# MCU_Ver1.net
KiCad netlist of a schematic drawn in Altium Designer
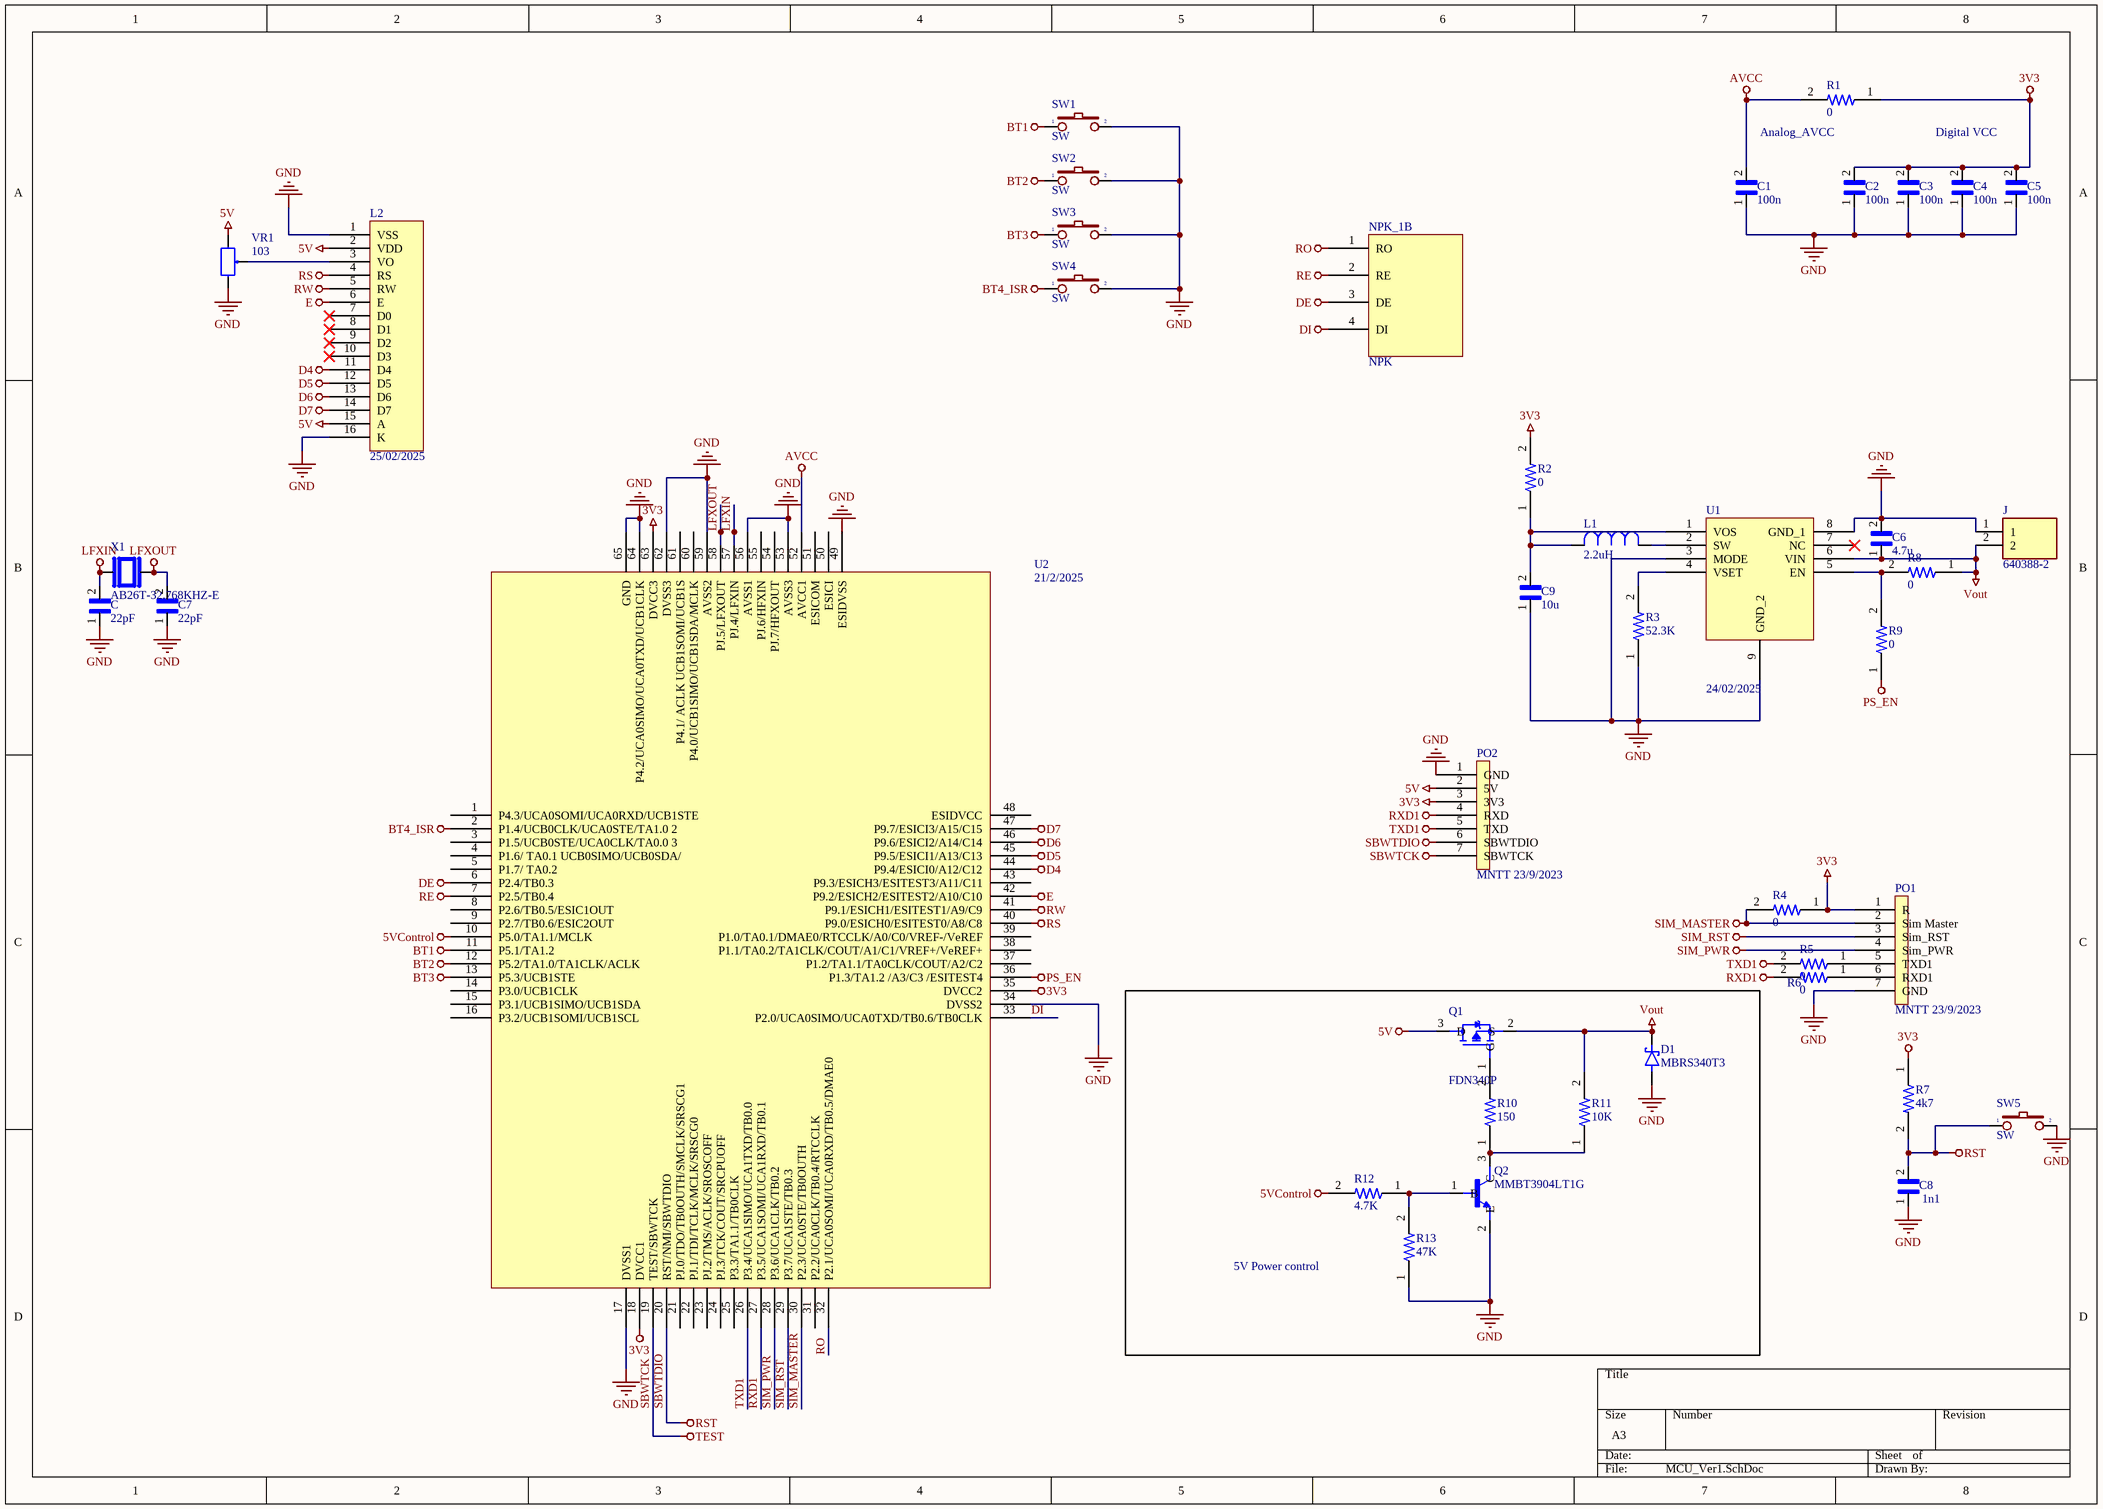
[diagram p0: MCU_Ver1.SchDoc]

(export (version "E")
  (design (tool "Eeschema 10.0.6"))
  (components
    (comp (ref "C")
      (value "22pF")
      (footprint "CAPC0603X33N")
      (description "SMD Capacitor X7R_EIA_ with Capacitance: 1000pF Tol. 10%. Rated Voltage: 50Vdc")
      (fields (field (name "DIGI-KEY_PART_NUMBER") "490-10682-1-ND") (field (name "MP") "GRM033R71H102KA12D"))
      (libsource (lib "GRM033R71H102KA12D") (part "GRM033R71H102KA12D"))
    )
    (comp (ref "C1")
      (value "100n")
      (footprint "CAPC0603X33N")
      (description "SMD Capacitor X7R_EIA_ with Capacitance: 1000pF Tol. 10%. Rated Voltage: 50Vdc")
      (fields (field (name "DIGI-KEY_PART_NUMBER") "490-10682-1-ND") (field (name "MP") "GRM033R71H102KA12D"))
      (libsource (lib "GRM033R71H102KA12D") (part "GRM033R71H102KA12D"))
    )
    (comp (ref "C2")
      (value "100n")
      (footprint "CAPC0603X33N")
      (description "SMD Capacitor X7R_EIA_ with Capacitance: 1000pF Tol. 10%. Rated Voltage: 50Vdc")
      (fields (field (name "DIGI-KEY_PART_NUMBER") "490-10682-1-ND") (field (name "MP") "GRM033R71H102KA12D"))
      (libsource (lib "GRM033R71H102KA12D") (part "GRM033R71H102KA12D"))
    )
    (comp (ref "C3")
      (value "100n")
      (footprint "CAPC0603X33N")
      (description "SMD Capacitor X7R_EIA_ with Capacitance: 1000pF Tol. 10%. Rated Voltage: 50Vdc")
      (fields (field (name "DIGI-KEY_PART_NUMBER") "490-10682-1-ND") (field (name "MP") "GRM033R71H102KA12D"))
      (libsource (lib "GRM033R71H102KA12D") (part "GRM033R71H102KA12D"))
    )
    (comp (ref "C4")
      (value "100n")
      (footprint "CAPC0603X33N")
      (description "SMD Capacitor X7R_EIA_ with Capacitance: 1000pF Tol. 10%. Rated Voltage: 50Vdc")
      (fields (field (name "DIGI-KEY_PART_NUMBER") "490-10682-1-ND") (field (name "MP") "GRM033R71H102KA12D"))
      (libsource (lib "GRM033R71H102KA12D") (part "GRM033R71H102KA12D"))
    )
    (comp (ref "C5")
      (value "100n")
      (footprint "CAPC0603X33N")
      (description "SMD Capacitor X7R_EIA_ with Capacitance: 1000pF Tol. 10%. Rated Voltage: 50Vdc")
      (fields (field (name "DIGI-KEY_PART_NUMBER") "490-10682-1-ND") (field (name "MP") "GRM033R71H102KA12D"))
      (libsource (lib "GRM033R71H102KA12D") (part "GRM033R71H102KA12D"))
    )
    (comp (ref "C6")
      (value "4.7u")
      (footprint "CAPC0603X33N")
      (description "SMD Capacitor X7R_EIA_ with Capacitance: 1000pF Tol. 10%. Rated Voltage: 50Vdc")
      (fields (field (name "DIGI-KEY_PART_NUMBER") "490-10682-1-ND") (field (name "MP") "GRM033R71H102KA12D"))
      (libsource (lib "GRM033R71H102KA12D") (part "GRM033R71H102KA12D"))
    )
    (comp (ref "C7")
      (value "22pF")
      (footprint "CAPC0603X33N")
      (description "SMD Capacitor X7R_EIA_ with Capacitance: 1000pF Tol. 10%. Rated Voltage: 50Vdc")
      (fields (field (name "DIGI-KEY_PART_NUMBER") "490-10682-1-ND") (field (name "MP") "GRM033R71H102KA12D"))
      (libsource (lib "GRM033R71H102KA12D") (part "GRM033R71H102KA12D"))
    )
    (comp (ref "C8")
      (value "1n1")
      (footprint "CAPC0603X33N")
      (description "SMD Capacitor X7R_EIA_ with Capacitance: 1000pF Tol. 10%. Rated Voltage: 50Vdc")
      (fields (field (name "DIGI-KEY_PART_NUMBER") "490-10682-1-ND") (field (name "MP") "GRM033R71H102KA12D"))
      (libsource (lib "GRM033R71H102KA12D") (part "GRM033R71H102KA12D"))
    )
    (comp (ref "C9")
      (value "10u")
      (footprint "CAPC0603X33N")
      (description "SMD Capacitor X7R_EIA_ with Capacitance: 1000pF Tol. 10%. Rated Voltage: 50Vdc")
      (fields (field (name "DIGI-KEY_PART_NUMBER") "490-10682-1-ND") (field (name "MP") "GRM033R71H102KA12D"))
      (libsource (lib "GRM033R71H102KA12D") (part "GRM033R71H102KA12D"))
    )
    (comp (ref "D1")
      (value "MBRS340T3")
      (footprint "DIOM7959X261N")
      (description "Diode Schottky 40V 4A Surface Mount SMC")
      (fields (field (name "MF") "ON Semiconductor"))
      (libsource (lib "MBRS340T3") (part "MBRS340T3"))
    )
    (comp (ref "J")
      (value "640388-2")
      (footprint "TE_640388-2")
      (description "Header; Conn; Interconnect System; PCB Plug; 2 Cont; Solder; MTA-156 Series; Straight")
      (fields (field (name "MF") "TE Connectivity"))
      (libsource (lib "640388-2") (part "640388-2"))
    )
    (comp (ref "L1")
      (value "2.2uH")
      (footprint "IND_CDRH127/LDNP-470MC_SUM")
      (description "47 ÂµH Shielded - Inductor 3.25 A 78mOhm Max Nonstandard")
      (fields (field (name "MF") "Sumida America") (field (name "MP") "CDRH127/LDNP-470MC"))
      (libsource (lib "CDRH127_LDNP-470MC") (part "CDRH127/LDNP-470MC"))
    )
    (comp (ref "L2")
      (value "25/02/2025")
      (footprint "PCBComponent_1")
      (libsource (lib "LCD1602") (part "LCD1602"))
    )
    (comp (ref "NPK_1")
      (value "NPK")
      (footprint "PCBComponent_1")
      (description "02/04/2024. NPK_?")
      (libsource (lib "NPK") (part "NPK"))
    )
    (comp (ref "PO1")
      (value "MNTT 23/9/2023")
      (footprint "PCBComponent_1")
      (libsource (lib "Port 7 pins") (part "Port 7 pins"))
    )
    (comp (ref "PO2")
      (value "MNTT 23/9/2023")
      (footprint "PCBComponent_1")
      (libsource (lib "Port 7 pins") (part "Port 7 pins"))
    )
    (comp (ref "Q1")
      (value "FDN340P")
      (footprint "SOT95P240X120-3N")
      (description "FDN340P Series 20V 70 mOhm Single P-Ch Logic Level PowerTrench Mosfet SSOT-3")
      (libsource (lib "FDN340P") (part "FDN340P"))
    )
    (comp (ref "Q2")
      (value "MMBT3904LT1G")
      (footprint "SOT95P240X111-3N")
      (description "Bipolar _BJT_ Transistor NPN 40V 200mA 300MHz 300mW Surface Mount SOT-23-3 _TO-236_")
      (fields (field (name "MF") "ON Semiconductor"))
      (libsource (lib "MMBT3904LT1G") (part "MMBT3904LT1G"))
    )
    (comp (ref "R1")
      (value "0")
      (footprint "RESC1608X50N")
      (description "RES SMD 180K OHM 5% 1/4W 0603")
      (fields (field (name "MP") "CRGS0603J180K"))
      (libsource (lib "CRGS0603J180K") (part "CRGS0603J180K"))
    )
    (comp (ref "R2")
      (value "0")
      (footprint "RESC1608X50N")
      (description "RES SMD 180K OHM 5% 1/4W 0603")
      (fields (field (name "MP") "CRGS0603J180K"))
      (libsource (lib "CRGS0603J180K") (part "CRGS0603J180K"))
    )
    (comp (ref "R3")
      (value "52.3K")
      (footprint "RESC1608X50N")
      (description "RES SMD 180K OHM 5% 1/4W 0603")
      (fields (field (name "MP") "CRGS0603J180K"))
      (libsource (lib "CRGS0603J180K") (part "CRGS0603J180K"))
    )
    (comp (ref "R4")
      (value "0")
      (footprint "RESC1608X50N")
      (description "RES SMD 180K OHM 5% 1/4W 0603")
      (fields (field (name "MP") "CRGS0603J180K"))
      (libsource (lib "CRGS0603J180K") (part "CRGS0603J180K"))
    )
    (comp (ref "R5")
      (value "0")
      (footprint "RESC1608X50N")
      (description "RES SMD 180K OHM 5% 1/4W 0603")
      (fields (field (name "MP") "CRGS0603J180K"))
      (libsource (lib "CRGS0603J180K") (part "CRGS0603J180K"))
    )
    (comp (ref "R6")
      (value "0")
      (footprint "RESC1608X50N")
      (description "RES SMD 180K OHM 5% 1/4W 0603")
      (fields (field (name "MP") "CRGS0603J180K"))
      (libsource (lib "CRGS0603J180K") (part "CRGS0603J180K"))
    )
    (comp (ref "R7")
      (value "4k7")
      (footprint "RESC1608X50N")
      (description "RES SMD 180K OHM 5% 1/4W 0603")
      (fields (field (name "MP") "CRGS0603J180K"))
      (libsource (lib "CRGS0603J180K") (part "CRGS0603J180K"))
    )
    (comp (ref "R8")
      (value "0")
      (footprint "RESC1608X50N")
      (description "RES SMD 180K OHM 5% 1/4W 0603")
      (fields (field (name "MP") "CRGS0603J180K"))
      (libsource (lib "CRGS0603J180K") (part "CRGS0603J180K"))
    )
    (comp (ref "R9")
      (value "0")
      (footprint "RESC1608X50N")
      (description "RES SMD 180K OHM 5% 1/4W 0603")
      (fields (field (name "MP") "CRGS0603J180K"))
      (libsource (lib "CRGS0603J180K") (part "CRGS0603J180K"))
    )
    (comp (ref "R10")
      (value "150")
      (footprint "CAPC0603X33N")
      (description "RES SMD 180K OHM 5% 1/4W 0603")
      (fields (field (name "MP") "CRGS0603J180K"))
      (libsource (lib "CRGS0603J180K") (part "CRGS0603J180K"))
    )
    (comp (ref "R11")
      (value "10K")
      (footprint "CAPC0603X33N")
      (description "RES SMD 180K OHM 5% 1/4W 0603")
      (fields (field (name "MP") "CRGS0603J180K"))
      (libsource (lib "CRGS0603J180K") (part "CRGS0603J180K"))
    )
    (comp (ref "R12")
      (value "4.7K")
      (footprint "CAPC0603X33N")
      (description "RES SMD 180K OHM 5% 1/4W 0603")
      (fields (field (name "MP") "CRGS0603J180K"))
      (libsource (lib "CRGS0603J180K") (part "CRGS0603J180K"))
    )
    (comp (ref "R13")
      (value "47K")
      (footprint "CAPC0603X33N")
      (description "RES SMD 180K OHM 5% 1/4W 0603")
      (fields (field (name "MP") "CRGS0603J180K"))
      (libsource (lib "CRGS0603J180K") (part "CRGS0603J180K"))
    )
    (comp (ref "SW1")
      (value "SW")
      (footprint "SW2")
      (description "Switch button 2 pin")
      (libsource (lib "syhaunguyen") (part "SW2"))
    )
    (comp (ref "SW2")
      (value "SW")
      (footprint "SW2")
      (description "Switch button 2 pin")
      (libsource (lib "syhaunguyen") (part "SW2"))
    )
    (comp (ref "SW3")
      (value "SW")
      (footprint "SW2")
      (description "Switch button 2 pin")
      (libsource (lib "syhaunguyen") (part "SW2"))
    )
    (comp (ref "SW4")
      (value "SW")
      (footprint "SW2")
      (description "Switch button 2 pin")
      (libsource (lib "syhaunguyen") (part "SW2"))
    )
    (comp (ref "SW5")
      (value "SW")
      (footprint "SW2")
      (description "Switch button 2 pin")
      (libsource (lib "syhaunguyen") (part "SW2"))
    )
    (comp (ref "U1")
      (value "24/02/2025")
      (footprint "SOP65P490X110-9N")
      (libsource (lib "TPS6282") (part "TPS62842DGRR"))
    )
    (comp (ref "U2")
      (value "21/2/2025")
      (footprint "IC_BQ500215RGCR")
      (libsource (lib "MSP430fr5989ver2") (part "MSP430FR5989_VER2"))
    )
    (comp (ref "VR1")
      (value "103")
      (footprint "VR")
      (description "Var Resistor")
      (libsource (lib "syhaunguyen") (part "VR"))
    )
    (comp (ref "X1")
      (value "AB26T-32.768KHZ-E")
      (footprint "XTAL_AB26T-32.768KHZ-E")
      (description "32.768kHz WATCH CRYSTAL, 6.2 x 02.1MM CYLINDER PACKAGE")
      (fields (field (name "MF") "Abracon LLC"))
      (libsource (lib "AB26T-32.768KHZ-E") (part "AB26T-32.768KHZ-E"))
    )
  )
  (nets
    (net (code "1") (name "3V3") (class "Default")
      (node (ref "C2") (pin "2") (pinfunction "2_2") (pintype "passive"))
      (node (ref "C3") (pin "2") (pinfunction "2_2") (pintype "passive"))
      (node (ref "C4") (pin "2") (pinfunction "2_2") (pintype "passive"))
      (node (ref "C5") (pin "2") (pinfunction "2_2") (pintype "passive"))
      (node (ref "PO1") (pin "1") (pinfunction "R_1") (pintype "passive"))
      (node (ref "PO2") (pin "3") (pinfunction "Sim_RST_3") (pintype "passive"))
      (node (ref "R1") (pin "1") (pinfunction "1_1") (pintype "passive"))
      (node (ref "R2") (pin "2") (pinfunction "2_2") (pintype "passive"))
      (node (ref "R4") (pin "1") (pinfunction "1_1") (pintype "passive"))
      (node (ref "R7") (pin "1") (pinfunction "1_1") (pintype "passive"))
      (node (ref "U2") (pin "18") (pinfunction "DVCC1_18") (pintype "passive"))
      (node (ref "U2") (pin "35") (pinfunction "DVCC2_35") (pintype "passive"))
      (node (ref "U2") (pin "63") (pinfunction "DVCC3_63") (pintype "passive"))
    )
    (net (code "2") (name "5V") (class "Default")
      (node (ref "L2") (pin "15") (pinfunction "A_15") (pintype "passive"))
      (node (ref "L2") (pin "2") (pinfunction "VDD_2") (pintype "passive"))
      (node (ref "PO2") (pin "2") (pinfunction "Sim_Master_2") (pintype "passive"))
      (node (ref "Q1") (pin "3") (pinfunction "D_3") (pintype "passive"))
      (node (ref "VR1") (pin "1") (pinfunction "1_1") (pintype "passive"))
    )
    (net (code "3") (name "5VControl") (class "Default")
      (node (ref "R12") (pin "2") (pinfunction "2_2") (pintype "passive"))
      (node (ref "U2") (pin "10") (pinfunction "P5.0/TA1.1/MCLK_10") (pintype "passive"))
    )
    (net (code "4") (name "AVCC") (class "Default")
      (node (ref "C1") (pin "2") (pinfunction "2_2") (pintype "passive"))
      (node (ref "R1") (pin "2") (pinfunction "2_2") (pintype "passive"))
      (node (ref "U2") (pin "52") (pinfunction "AVCC1_52") (pintype "passive"))
    )
    (net (code "5") (name "BT1") (class "Default")
      (node (ref "SW1") (pin "1") (pinfunction "1_1") (pintype "passive"))
      (node (ref "U2") (pin "11") (pinfunction "P5.1/TA1.2_11") (pintype "passive"))
    )
    (net (code "6") (name "BT2") (class "Default")
      (node (ref "SW2") (pin "1") (pinfunction "1_1") (pintype "passive"))
      (node (ref "U2") (pin "12") (pinfunction "P5.2/TA1.0/TA1CLK/ACLK_12") (pintype "passive"))
    )
    (net (code "7") (name "BT3") (class "Default")
      (node (ref "SW3") (pin "1") (pinfunction "1_1") (pintype "passive"))
      (node (ref "U2") (pin "13") (pinfunction "P5.3/UCB1STE_13") (pintype "passive"))
    )
    (net (code "8") (name "BT4_ISR") (class "Default")
      (node (ref "SW4") (pin "1") (pinfunction "1_1") (pintype "passive"))
      (node (ref "U2") (pin "2") (pinfunction "P1.4/UCB0CLK/UCA0STE/TA1.0_2_2") (pintype "passive"))
    )
    (net (code "9") (name "D4") (class "Default")
      (node (ref "L2") (pin "11") (pinfunction "D4_11") (pintype "passive"))
      (node (ref "U2") (pin "44") (pinfunction "_P9.4/ESICI0/A12/C12_44") (pintype "passive"))
    )
    (net (code "10") (name "D5") (class "Default")
      (node (ref "L2") (pin "12") (pinfunction "D5_12") (pintype "passive"))
      (node (ref "U2") (pin "45") (pinfunction "P9.5/ESICI1/A13/C13_45") (pintype "passive"))
    )
    (net (code "11") (name "D6") (class "Default")
      (node (ref "L2") (pin "13") (pinfunction "D6_13") (pintype "passive"))
      (node (ref "U2") (pin "46") (pinfunction "_P9.6/ESICI2/A14/C14_46") (pintype "passive"))
    )
    (net (code "12") (name "D7") (class "Default")
      (node (ref "L2") (pin "14") (pinfunction "D7_14") (pintype "passive"))
      (node (ref "U2") (pin "47") (pinfunction "P9.7/ESICI3/A15/C15_47") (pintype "passive"))
    )
    (net (code "13") (name "DE") (class "Default")
      (node (ref "NPK_1") (pin "3") (pinfunction "DE_3") (pintype "passive"))
      (node (ref "U2") (pin "6") (pinfunction "P2.4/TB0.3_6") (pintype "passive"))
    )
    (net (code "14") (name "DI") (class "Default")
      (node (ref "NPK_1") (pin "4") (pinfunction "DI_4") (pintype "passive"))
      (node (ref "U2") (pin "33") (pinfunction "P2.0/UCA0SIMO/UCA0TXD/TB0.6/TB0CLK_33") (pintype "passive"))
    )
    (net (code "15") (name "E") (class "Default")
      (node (ref "L2") (pin "6") (pinfunction "E_6") (pintype "passive"))
      (node (ref "U2") (pin "42") (pinfunction "_P9.2/ESICH2/ESITEST2/A10/C10_42") (pintype "passive"))
    )
    (net (code "16") (name "GND") (class "Default")
      (node (ref "C") (pin "1") (pinfunction "1_1") (pintype "passive"))
      (node (ref "C1") (pin "1") (pinfunction "1_1") (pintype "passive"))
      (node (ref "C2") (pin "1") (pinfunction "1_1") (pintype "passive"))
      (node (ref "C3") (pin "1") (pinfunction "1_1") (pintype "passive"))
      (node (ref "C4") (pin "1") (pinfunction "1_1") (pintype "passive"))
      (node (ref "C5") (pin "1") (pinfunction "1_1") (pintype "passive"))
      (node (ref "C6") (pin "2") (pinfunction "2_2") (pintype "passive"))
      (node (ref "C7") (pin "1") (pinfunction "1_1") (pintype "passive"))
      (node (ref "C8") (pin "1") (pinfunction "1_1") (pintype "passive"))
      (node (ref "C9") (pin "1") (pinfunction "1_1") (pintype "passive"))
      (node (ref "D1") (pin "A") (pinfunction "A_A") (pintype "passive"))
      (node (ref "J") (pin "1") (pinfunction "1_1") (pintype "passive"))
      (node (ref "L2") (pin "1") (pinfunction "VSS_1") (pintype "passive"))
      (node (ref "L2") (pin "16") (pinfunction "K_16") (pintype "passive"))
      (node (ref "PO1") (pin "7") (pinfunction "GND_7") (pintype "passive"))
      (node (ref "PO2") (pin "1") (pinfunction "R_1") (pintype "passive"))
      (node (ref "Q2") (pin "2") (pinfunction "E_2") (pintype "passive"))
      (node (ref "R13") (pin "1") (pinfunction "1_1") (pintype "passive"))
      (node (ref "R3") (pin "1") (pinfunction "1_1") (pintype "passive"))
      (node (ref "SW1") (pin "2") (pinfunction "2_2") (pintype "passive"))
      (node (ref "SW2") (pin "2") (pinfunction "2_2") (pintype "passive"))
      (node (ref "SW3") (pin "2") (pinfunction "2_2") (pintype "passive"))
      (node (ref "SW4") (pin "2") (pinfunction "2_2") (pintype "passive"))
      (node (ref "SW5") (pin "2") (pinfunction "2_2") (pintype "passive"))
      (node (ref "U1") (pin "3") (pinfunction "MODE_3") (pintype "passive"))
      (node (ref "U1") (pin "8") (pinfunction "GND_1_8") (pintype "passive"))
      (node (ref "U1") (pin "9") (pinfunction "GND_2_9") (pintype "passive"))
      (node (ref "U2") (pin "17") (pinfunction "DVSS1_17") (pintype "passive"))
      (node (ref "U2") (pin "34") (pinfunction "DVSS2_34") (pintype "passive"))
      (node (ref "U2") (pin "49") (pinfunction "ESIDVSS_49") (pintype "passive"))
      (node (ref "U2") (pin "53") (pinfunction "AVSS3_53") (pintype "passive"))
      (node (ref "U2") (pin "56") (pinfunction "AVSS1_56") (pintype "passive"))
      (node (ref "U2") (pin "59") (pinfunction "AVSS2_59") (pintype "passive"))
      (node (ref "U2") (pin "62") (pinfunction "DVSS3_62") (pintype "passive"))
      (node (ref "U2") (pin "64") (pinfunction "P4.2/UCA0SIMO/UCA0TXD/UCB1CLK_64") (pintype "passive"))
      (node (ref "U2") (pin "65") (pinfunction "GND_65") (pintype "passive"))
      (node (ref "VR1") (pin "3") (pinfunction "3_3") (pintype "passive"))
    )
    (net (code "17") (name "LFXIN") (class "Default")
      (node (ref "C") (pin "2") (pinfunction "2_2") (pintype "passive"))
      (node (ref "U2") (pin "57") (pinfunction "PJ.4/LFXIN_57") (pintype "passive"))
      (node (ref "X1") (pin "1") (pinfunction "1_1") (pintype "passive"))
    )
    (net (code "18") (name "LFXOUT") (class "Default")
      (node (ref "C7") (pin "2") (pinfunction "2_2") (pintype "passive"))
      (node (ref "U2") (pin "58") (pinfunction "PJ.5/LFXOUT_58") (pintype "passive"))
      (node (ref "X1") (pin "2") (pinfunction "2_2") (pintype "passive"))
    )
    (net (code "19") (name "Net-(L2-VO)") (class "Default")
      (node (ref "L2") (pin "3") (pinfunction "VO_3") (pintype "passive"))
      (node (ref "VR1") (pin "2") (pinfunction "2_2") (pintype "passive"))
    )
    (net (code "20") (name "Net-(PO1-RXD1)") (class "Default")
      (node (ref "PO1") (pin "6") (pinfunction "RXD1_6") (pintype "passive"))
      (node (ref "R6") (pin "1") (pinfunction "1_1") (pintype "passive"))
    )
    (net (code "21") (name "Net-(PO1-TXD1)") (class "Default")
      (node (ref "PO1") (pin "5") (pinfunction "TXD1_5") (pintype "passive"))
      (node (ref "R5") (pin "1") (pinfunction "1_1") (pintype "passive"))
    )
    (net (code "22") (name "Net-(Q1-G)") (class "Default")
      (node (ref "Q1") (pin "1") (pinfunction "G_1") (pintype "passive"))
      (node (ref "R10") (pin "2") (pinfunction "2_2") (pintype "passive"))
    )
    (net (code "23") (name "Net-(Q2-B)") (class "Default")
      (node (ref "Q2") (pin "1") (pinfunction "B_1") (pintype "passive"))
      (node (ref "R12") (pin "1") (pinfunction "1_1") (pintype "passive"))
      (node (ref "R13") (pin "2") (pinfunction "2_2") (pintype "passive"))
    )
    (net (code "24") (name "Net-(Q2-C)") (class "Default")
      (node (ref "Q2") (pin "3") (pinfunction "C_3") (pintype "passive"))
      (node (ref "R10") (pin "1") (pinfunction "1_1") (pintype "passive"))
      (node (ref "R11") (pin "1") (pinfunction "1_1") (pintype "passive"))
    )
    (net (code "25") (name "Net-(U1-EN)") (class "Default")
      (node (ref "R8") (pin "2") (pinfunction "2_2") (pintype "passive"))
      (node (ref "R9") (pin "2") (pinfunction "2_2") (pintype "passive"))
      (node (ref "U1") (pin "5") (pinfunction "EN_5") (pintype "passive"))
    )
    (net (code "26") (name "Net-(U1-SW)") (class "Default")
      (node (ref "L1") (pin "1") (pinfunction "1_1") (pintype "passive"))
      (node (ref "U1") (pin "2") (pinfunction "SW_2") (pintype "passive"))
    )
    (net (code "27") (name "Net-(U1-VOS)") (class "Default")
      (node (ref "C9") (pin "2") (pinfunction "2_2") (pintype "passive"))
      (node (ref "L1") (pin "2") (pinfunction "2_2") (pintype "passive"))
      (node (ref "R2") (pin "1") (pinfunction "1_1") (pintype "passive"))
      (node (ref "U1") (pin "1") (pinfunction "VOS_1") (pintype "passive"))
    )
    (net (code "28") (name "Net-(U1-VSET)") (class "Default")
      (node (ref "R3") (pin "2") (pinfunction "2_2") (pintype "passive"))
      (node (ref "U1") (pin "4") (pinfunction "VSET_4") (pintype "passive"))
    )
    (net (code "29") (name "PS_EN") (class "Default")
      (node (ref "R9") (pin "1") (pinfunction "1_1") (pintype "passive"))
      (node (ref "U2") (pin "36") (pinfunction "P1.3/TA1.2_/A3/C3_/ESITEST4_36") (pintype "passive"))
    )
    (net (code "30") (name "RE") (class "Default")
      (node (ref "NPK_1") (pin "2") (pinfunction "RE_2") (pintype "passive"))
      (node (ref "U2") (pin "7") (pinfunction "P2.5/TB0.4_7") (pintype "passive"))
    )
    (net (code "31") (name "RO") (class "Default")
      (node (ref "NPK_1") (pin "1") (pinfunction "RO_1") (pintype "passive"))
      (node (ref "U2") (pin "32") (pinfunction "P2.1/UCA0SOMI/UCA0RXD/TB0.5/DMAE0_32") (pintype "passive"))
    )
    (net (code "32") (name "RS") (class "Default")
      (node (ref "L2") (pin "4") (pinfunction "RS_4") (pintype "passive"))
      (node (ref "U2") (pin "40") (pinfunction "P9.0/ESICH0/ESITEST0/A8/C8_40") (pintype "passive"))
    )
    (net (code "33") (name "RST") (class "Default")
      (node (ref "C8") (pin "2") (pinfunction "2_2") (pintype "passive"))
      (node (ref "PO2") (pin "6") (pinfunction "RXD1_6") (pintype "passive"))
      (node (ref "R7") (pin "2") (pinfunction "2_2") (pintype "passive"))
      (node (ref "SW5") (pin "1") (pinfunction "1_1") (pintype "passive"))
      (node (ref "U2") (pin "20") (pinfunction "RST/NMI/SBWTDIO_20") (pintype "passive"))
    )
    (net (code "34") (name "RW") (class "Default")
      (node (ref "L2") (pin "5") (pinfunction "RW_5") (pintype "passive"))
      (node (ref "U2") (pin "41") (pinfunction "P9.1/ESICH1/ESITEST1/A9/C9_41") (pintype "passive"))
    )
    (net (code "35") (name "RXD1") (class "Default")
      (node (ref "PO2") (pin "4") (pinfunction "Sim_PWR_4") (pintype "passive"))
      (node (ref "R6") (pin "2") (pinfunction "2_2") (pintype "passive"))
      (node (ref "U2") (pin "27") (pinfunction "P3.5/UCA1SOMI/UCA1RXD/TB0.1_27") (pintype "passive"))
    )
    (net (code "36") (name "SBWTCK") (class "Default")
      (node (ref "PO2") (pin "7") (pinfunction "GND_7") (pintype "passive"))
      (node (ref "U2") (pin "19") (pinfunction "TEST/SBWTCK_19") (pintype "passive"))
    )
    (net (code "37") (name "SIM_MASTER") (class "Default")
      (node (ref "PO1") (pin "2") (pinfunction "Sim_Master_2") (pintype "passive"))
      (node (ref "R4") (pin "2") (pinfunction "2_2") (pintype "passive"))
      (node (ref "U2") (pin "30") (pinfunction "P2.3/UCA0STE/TB0OUTH_30") (pintype "passive"))
    )
    (net (code "38") (name "SIM_PWR") (class "Default")
      (node (ref "PO1") (pin "4") (pinfunction "Sim_PWR_4") (pintype "passive"))
      (node (ref "U2") (pin "28") (pinfunction "P3.6/UCA1CLK/TB0.2_28") (pintype "passive"))
    )
    (net (code "39") (name "SIM_RST") (class "Default")
      (node (ref "PO1") (pin "3") (pinfunction "Sim_RST_3") (pintype "passive"))
      (node (ref "U2") (pin "29") (pinfunction "P3.7/UCA1STE/TB0.3_29") (pintype "passive"))
    )
    (net (code "40") (name "TXD1") (class "Default")
      (node (ref "PO2") (pin "5") (pinfunction "TXD1_5") (pintype "passive"))
      (node (ref "R5") (pin "2") (pinfunction "2_2") (pintype "passive"))
      (node (ref "U2") (pin "26") (pinfunction "P3.4/UCA1SIMO/UCA1TXD/TB0.0_26") (pintype "passive"))
    )
    (net (code "41") (name "Vout") (class "Default")
      (node (ref "C6") (pin "1") (pinfunction "1_1") (pintype "passive"))
      (node (ref "D1") (pin "C") (pinfunction "K_C") (pintype "passive"))
      (node (ref "J") (pin "2") (pinfunction "2_2") (pintype "passive"))
      (node (ref "Q1") (pin "2") (pinfunction "S_2") (pintype "passive"))
      (node (ref "R11") (pin "2") (pinfunction "2_2") (pintype "passive"))
      (node (ref "R8") (pin "1") (pinfunction "1_1") (pintype "passive"))
      (node (ref "U1") (pin "6") (pinfunction "VIN_6") (pintype "passive"))
    )
    (net (code "42") (name "unconnected-(L2-D0-Pad7)") (class "Default")
      (node (ref "L2") (pin "7") (pinfunction "D0_7") (pintype "passive+no_connect"))
    )
    (net (code "43") (name "unconnected-(L2-D1-Pad8)") (class "Default")
      (node (ref "L2") (pin "8") (pinfunction "D1_8") (pintype "passive+no_connect"))
    )
    (net (code "44") (name "unconnected-(L2-D2-Pad9)") (class "Default")
      (node (ref "L2") (pin "9") (pinfunction "D2_9") (pintype "passive+no_connect"))
    )
    (net (code "45") (name "unconnected-(L2-D3-Pad10)") (class "Default")
      (node (ref "L2") (pin "10") (pinfunction "D3_10") (pintype "passive+no_connect"))
    )
    (net (code "46") (name "unconnected-(U1-NC-Pad7)") (class "Default")
      (node (ref "U1") (pin "7") (pinfunction "NC_7") (pintype "passive+no_connect"))
    )
    (net (code "47") (name "unconnected-(U2-ESICI-Pad50)") (class "Default")
      (node (ref "U2") (pin "50") (pinfunction "ESICI_50") (pintype "passive"))
    )
    (net (code "48") (name "unconnected-(U2-ESICOM-Pad51)") (class "Default")
      (node (ref "U2") (pin "51") (pinfunction "ESICOM_51") (pintype "passive"))
    )
    (net (code "49") (name "unconnected-(U2-ESIDVCC-Pad48)") (class "Default")
      (node (ref "U2") (pin "48") (pinfunction "ESIDVCC_48") (pintype "passive"))
    )
    (net (code "50") (name "unconnected-(U2-P1.0{slash}TA0.1{slash}DMAE0{slash}RTCCLK{slash}A0{slash}C0{slash}VREF-{slash}VeREF-Pad39)") (class "Default")
      (node (ref "U2") (pin "39") (pinfunction "P1.0/TA0.1/DMAE0/RTCCLK/A0/C0/VREF-/VeREF_39") (pintype "passive"))
    )
    (net (code "51") (name "unconnected-(U2-P1.2{slash}TA1.1{slash}TA0CLK{slash}COUT{slash}A2{slash}C2-Pad37)") (class "Default")
      (node (ref "U2") (pin "37") (pinfunction "P1.2/TA1.1/TA0CLK/COUT/A2/C2_37") (pintype "passive"))
    )
    (net (code "52") (name "unconnected-(U2-P1.5{slash}UCB0STE{slash}UCA0CLK{slash}TA0.0_3-Pad3)") (class "Default")
      (node (ref "U2") (pin "3") (pinfunction "P1.5/UCB0STE/UCA0CLK/TA0.0_3_3") (pintype "passive"))
    )
    (net (code "53") (name "unconnected-(U2-P1.6{slash}_TA0.1_UCB0SIMO{slash}UCB0SDA{slash}-Pad4)") (class "Default")
      (node (ref "U2") (pin "4") (pinfunction "P1.6/_TA0.1_UCB0SIMO/UCB0SDA/_4") (pintype "passive"))
    )
    (net (code "54") (name "unconnected-(U2-P1.7{slash}_TA0.2-Pad5)") (class "Default")
      (node (ref "U2") (pin "5") (pinfunction "P1.7/_TA0.2_5") (pintype "passive"))
    )
    (net (code "55") (name "unconnected-(U2-P2.2{slash}UCA0CLK{slash}TB0.4{slash}RTCCLK-Pad31)") (class "Default")
      (node (ref "U2") (pin "31") (pinfunction "P2.2/UCA0CLK/TB0.4/RTCCLK_31") (pintype "passive"))
    )
    (net (code "56") (name "unconnected-(U2-P2.6{slash}TB0.5{slash}ESIC1OUT-Pad8)") (class "Default")
      (node (ref "U2") (pin "8") (pinfunction "P2.6/TB0.5/ESIC1OUT_8") (pintype "passive"))
    )
    (net (code "57") (name "unconnected-(U2-P2.7{slash}TB0.6{slash}ESIC2OUT-Pad9)") (class "Default")
      (node (ref "U2") (pin "9") (pinfunction "P2.7/TB0.6/ESIC2OUT_9") (pintype "passive"))
    )
    (net (code "58") (name "unconnected-(U2-P3.0{slash}UCB1CLK-Pad14)") (class "Default")
      (node (ref "U2") (pin "14") (pinfunction "P3.0/UCB1CLK_14") (pintype "passive"))
    )
    (net (code "59") (name "unconnected-(U2-P3.1{slash}UCB1SIMO{slash}UCB1SDA-Pad15)") (class "Default")
      (node (ref "U2") (pin "15") (pinfunction "P3.1/UCB1SIMO/UCB1SDA_15") (pintype "passive"))
    )
    (net (code "60") (name "unconnected-(U2-P3.2{slash}UCB1SOMI{slash}UCB1SCL-Pad16)") (class "Default")
      (node (ref "U2") (pin "16") (pinfunction "P3.2/UCB1SOMI/UCB1SCL_16") (pintype "passive"))
    )
    (net (code "61") (name "unconnected-(U2-P3.3{slash}TA1.1{slash}TB0CLK-Pad25)") (class "Default")
      (node (ref "U2") (pin "25") (pinfunction "P3.3/TA1.1/TB0CLK_25") (pintype "passive"))
    )
    (net (code "62") (name "unconnected-(U2-P4.0{slash}UCB1SIMO{slash}UCB1SDA{slash}MCLK-Pad60)") (class "Default")
      (node (ref "U2") (pin "60") (pinfunction "P4.0/UCB1SIMO/UCB1SDA/MCLK_60") (pintype "passive"))
    )
    (net (code "63") (name "unconnected-(U2-P4.1{slash}_ACLK_UCB1SOMI{slash}UCB1S-Pad61)") (class "Default")
      (node (ref "U2") (pin "61") (pinfunction "P4.1/_ACLK_UCB1SOMI/UCB1S_61") (pintype "passive"))
    )
    (net (code "64") (name "unconnected-(U2-P4.3{slash}UCA0SOMI{slash}UCA0RXD{slash}UCB1STE-Pad1)") (class "Default")
      (node (ref "U2") (pin "1") (pinfunction "P4.3/UCA0SOMI/UCA0RXD/UCB1STE_1") (pintype "passive"))
    )
    (net (code "65") (name "unconnected-(U2-PJ.0{slash}TDO{slash}TB0OUTH{slash}SMCLK{slash}SRSCG1-Pad21)") (class "Default")
      (node (ref "U2") (pin "21") (pinfunction "PJ.0/TDO/TB0OUTH/SMCLK/SRSCG1_21") (pintype "passive"))
    )
    (net (code "66") (name "unconnected-(U2-PJ.1{slash}TDI{slash}TCLK{slash}MCLK{slash}SRSCG0-Pad22)") (class "Default")
      (node (ref "U2") (pin "22") (pinfunction "PJ.1/TDI/TCLK/MCLK/SRSCG0_22") (pintype "passive"))
    )
    (net (code "67") (name "unconnected-(U2-PJ.2{slash}TMS{slash}ACLK{slash}SROSCOFF-Pad23)") (class "Default")
      (node (ref "U2") (pin "23") (pinfunction "PJ.2/TMS/ACLK/SROSCOFF_23") (pintype "passive"))
    )
    (net (code "68") (name "unconnected-(U2-PJ.3{slash}TCK{slash}COUT{slash}SRCPUOFF-Pad24)") (class "Default")
      (node (ref "U2") (pin "24") (pinfunction "PJ.3/TCK/COUT/SRCPUOFF_24") (pintype "passive"))
    )
    (net (code "69") (name "unconnected-(U2-PJ.6{slash}HFXIN-Pad55)") (class "Default")
      (node (ref "U2") (pin "55") (pinfunction "PJ.6/HFXIN_55") (pintype "passive"))
    )
    (net (code "70") (name "unconnected-(U2-PJ.7{slash}HFXOUT-Pad54)") (class "Default")
      (node (ref "U2") (pin "54") (pinfunction "PJ.7/HFXOUT_54") (pintype "passive"))
    )
    (net (code "71") (name "unconnected-(U2-_P1.1{slash}TA0.2{slash}TA1CLK{slash}COUT{slash}A1{slash}C1{slash}VREF+{slash}VeREF+-Pad38)") (class "Default")
      (node (ref "U2") (pin "38") (pinfunction "_P1.1/TA0.2/TA1CLK/COUT/A1/C1/VREF+/VeREF+_38") (pintype "passive"))
    )
    (net (code "72") (name "unconnected-(U2-_P9.3{slash}ESICH3{slash}ESITEST3{slash}A11{slash}C11-Pad43)") (class "Default")
      (node (ref "U2") (pin "43") (pinfunction "_P9.3/ESICH3/ESITEST3/A11/C11_43") (pintype "passive"))
    )
  )
)
